# STC.net
KiCad netlist of a schematic drawn in Altium Designer
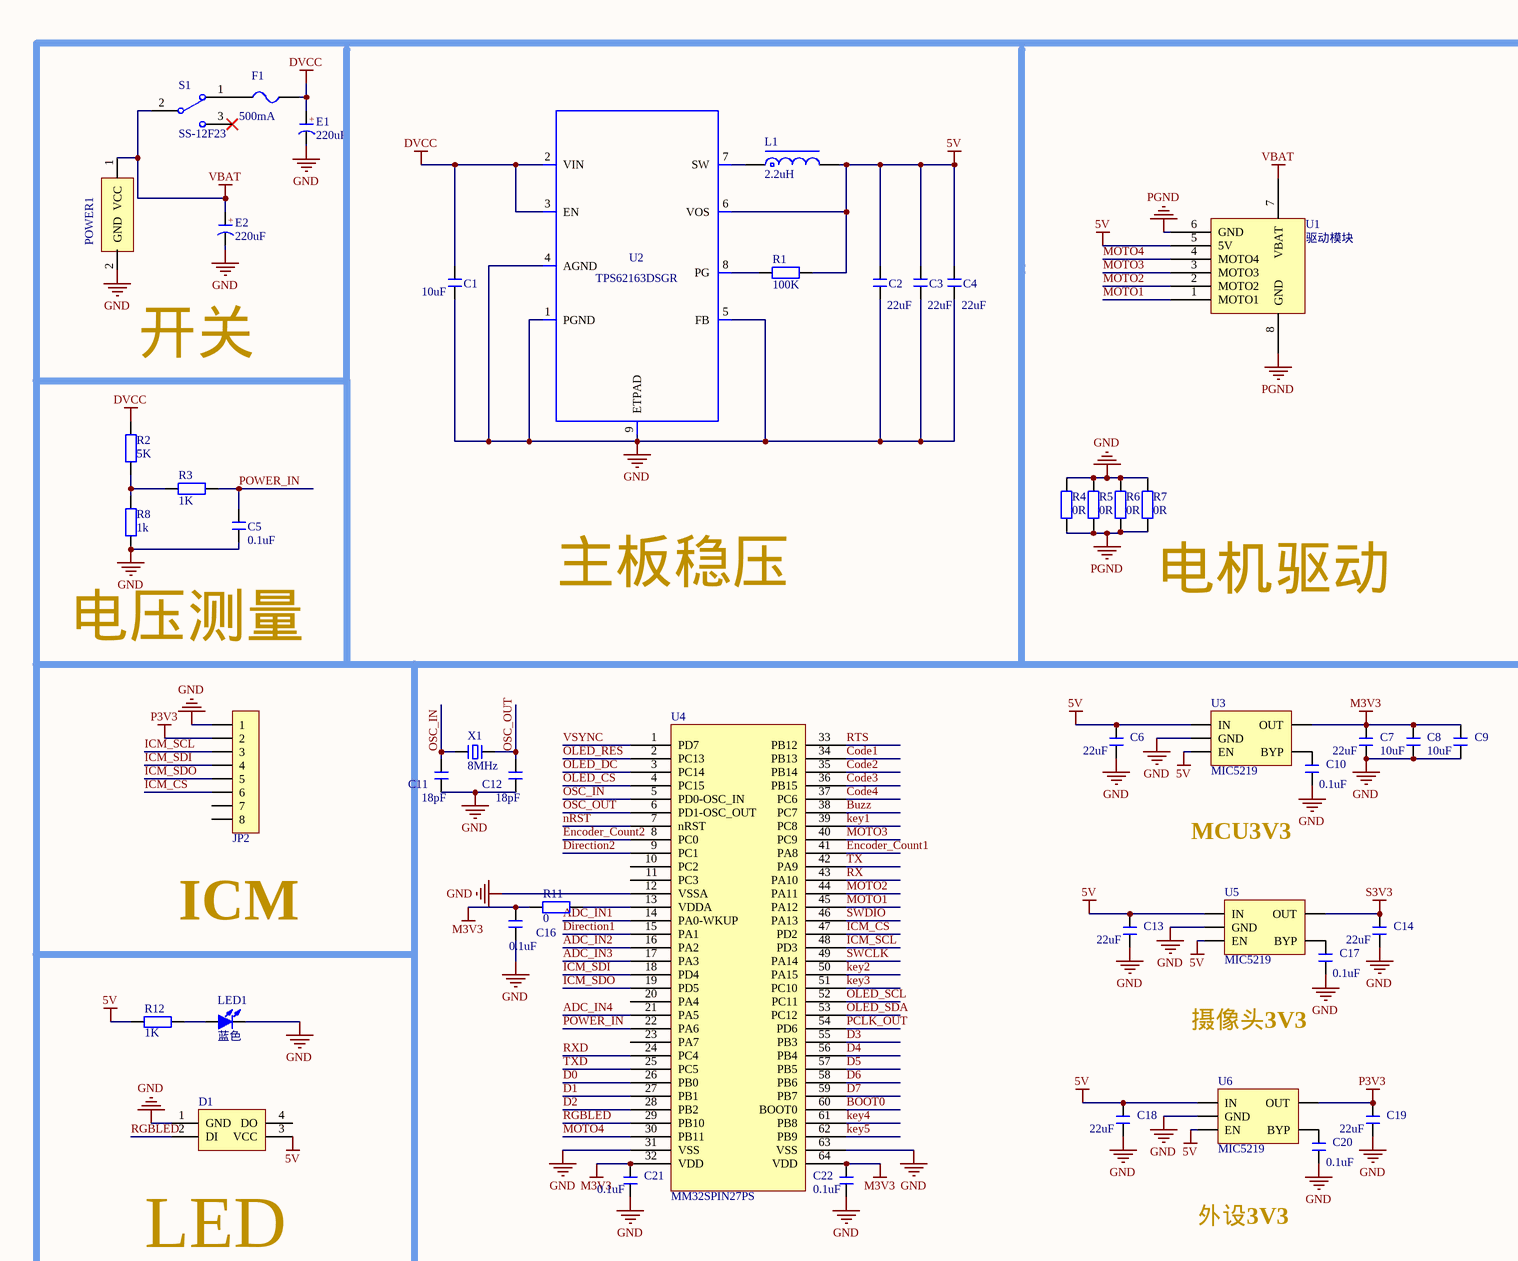
[diagram p0: STC智能车.SchDoc, top left]
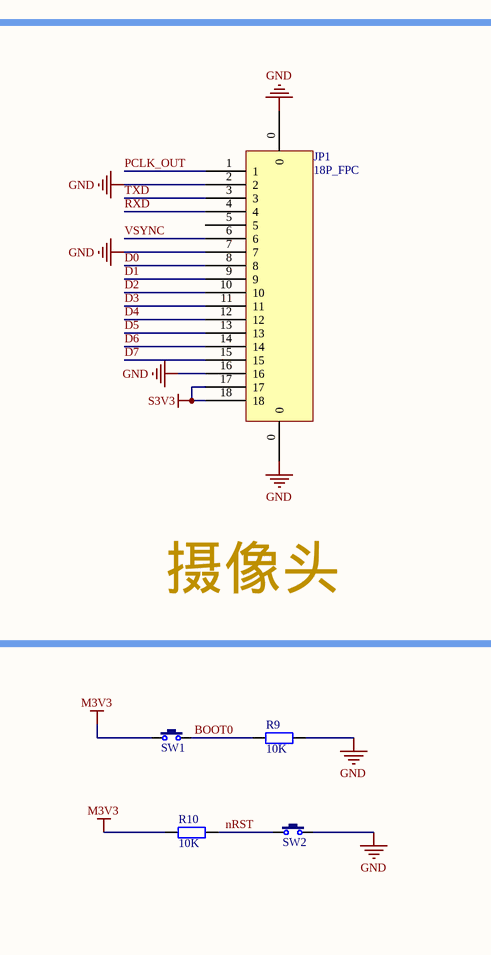
[diagram p1: STC智能车.SchDoc, top right]
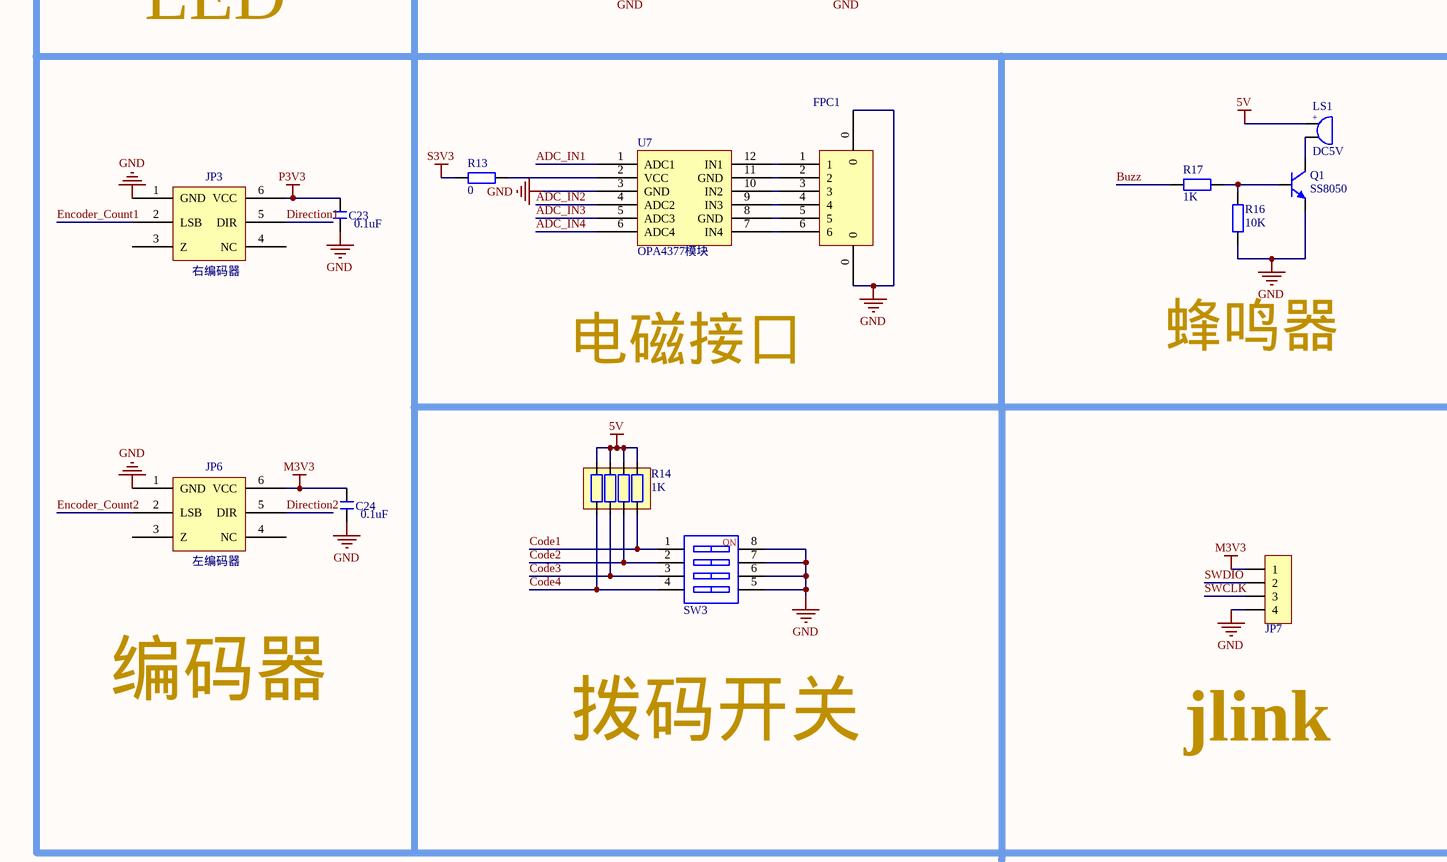
[diagram p2: STC智能车.SchDoc, bottom left]
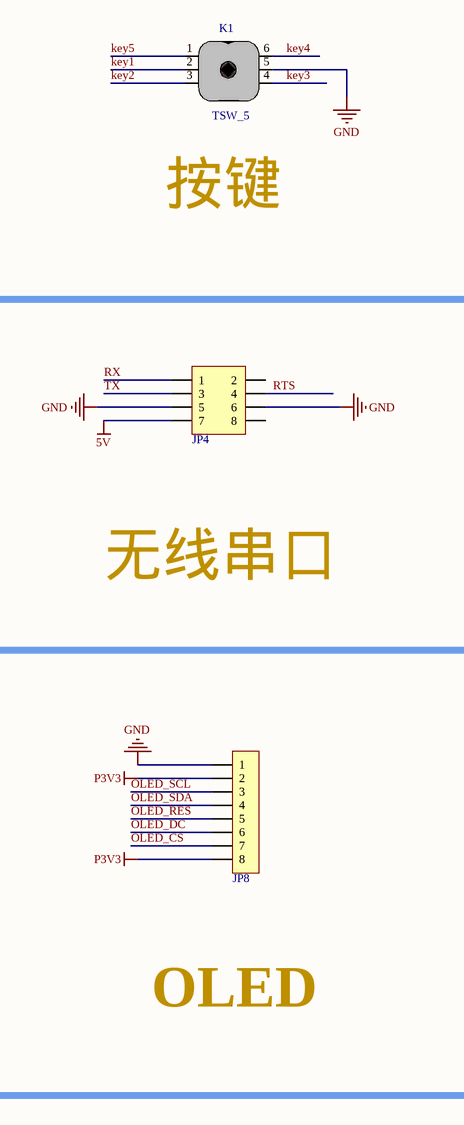
[diagram p3: STC智能车.SchDoc, bottom right]

(export (version "E")
  (design (tool "Eeschema 10.0.6"))
  (components
    (comp (ref "C1")
      (value "10uF")
      (footprint "C 0805_M")
      (description "贴片电容")
      (libsource (lib "0.1 - 电阻-电容-电感") (part "C"))
    )
    (comp (ref "C2")
      (value "22uF")
      (footprint "C 0805_M")
      (description "贴片电容")
      (libsource (lib "0.1 - 电阻-电容-电感") (part "C"))
    )
    (comp (ref "C3")
      (value "22uF")
      (footprint "C 0805_M")
      (description "贴片电容")
      (libsource (lib "0.1 - 电阻-电容-电感") (part "C"))
    )
    (comp (ref "C4")
      (value "22uF")
      (footprint "C 0805_M")
      (description "贴片电容")
      (libsource (lib "0.1 - 电阻-电容-电感") (part "C"))
    )
    (comp (ref "C5")
      (value "0.1uF")
      (footprint "C 0805_M")
      (description "贴片电容")
      (libsource (lib "0.1 - 电阻-电容-电感") (part "C"))
    )
    (comp (ref "C6")
      (value "22uF")
      (footprint "C 0805_M")
      (description "贴片电容")
      (libsource (lib "0.1 - 电阻-电容-电感") (part "C"))
    )
    (comp (ref "C7")
      (value "22uF")
      (footprint "C 0805_M")
      (description "贴片电容")
      (libsource (lib "0.1 - 电阻-电容-电感") (part "C"))
    )
    (comp (ref "C8")
      (value "10uF")
      (footprint "C 0805_M")
      (description "贴片电容")
      (libsource (lib "0.1 - 电阻-电容-电感") (part "C"))
    )
    (comp (ref "C9")
      (value "10uF")
      (footprint "C 0805_M")
      (description "贴片电容")
      (libsource (lib "0.1 - 电阻-电容-电感") (part "C"))
    )
    (comp (ref "C10")
      (value "0.1uF")
      (footprint "C 0805_M")
      (description "贴片电容")
      (libsource (lib "0.1 - 电阻-电容-电感") (part "C"))
    )
    (comp (ref "C11")
      (value "18pF")
      (footprint "C 0805_M")
      (description "贴片电容")
      (libsource (lib "0.1 - 电阻-电容-电感") (part "C"))
    )
    (comp (ref "C12")
      (value "18pF")
      (footprint "C 0805_M")
      (description "贴片电容")
      (libsource (lib "0.1 - 电阻-电容-电感") (part "C"))
    )
    (comp (ref "C13")
      (value "22uF")
      (footprint "C 0805_M")
      (description "贴片电容")
      (libsource (lib "0.1 - 电阻-电容-电感") (part "C"))
    )
    (comp (ref "C14")
      (value "22uF")
      (footprint "C 0805_M")
      (description "贴片电容")
      (libsource (lib "0.1 - 电阻-电容-电感") (part "C"))
    )
    (comp (ref "C16")
      (value "0.1uF")
      (footprint "C 0805_M")
      (description "贴片电容")
      (libsource (lib "0.1 - 电阻-电容-电感") (part "C"))
    )
    (comp (ref "C17")
      (value "0.1uF")
      (footprint "C 0805_M")
      (description "贴片电容")
      (libsource (lib "0.1 - 电阻-电容-电感") (part "C"))
    )
    (comp (ref "C18")
      (value "22uF")
      (footprint "C 0805_M")
      (description "贴片电容")
      (libsource (lib "0.1 - 电阻-电容-电感") (part "C"))
    )
    (comp (ref "C19")
      (value "22uF")
      (footprint "C 0805_M")
      (description "贴片电容")
      (libsource (lib "0.1 - 电阻-电容-电感") (part "C"))
    )
    (comp (ref "C20")
      (value "0.1uF")
      (footprint "C 0805_M")
      (description "贴片电容")
      (libsource (lib "0.1 - 电阻-电容-电感") (part "C"))
    )
    (comp (ref "C21")
      (value "0.1uF")
      (footprint "C 0805_M")
      (description "贴片电容")
      (libsource (lib "0.1 - 电阻-电容-电感") (part "C"))
    )
    (comp (ref "C22")
      (value "0.1uF")
      (footprint "C 0805_M")
      (description "贴片电容")
      (libsource (lib "0.1 - 电阻-电容-电感") (part "C"))
    )
    (comp (ref "C23")
      (value "0.1uF")
      (footprint "C 0805_M")
      (description "贴片电容")
      (libsource (lib "0.1 - 电阻-电容-电感") (part "C"))
    )
    (comp (ref "C24")
      (value "0.1uF")
      (footprint "C 0805_M")
      (description "贴片电容")
      (libsource (lib "0.1 - 电阻-电容-电感") (part "C"))
    )
    (comp (ref "D1")
      (value "P923D")
      (footprint "RGB_LED_5050")
      (fields (field (name "PUBLISHER") "mazhongwei"))
      (libsource (lib "RoboFly") (part "P923D"))
    )
    (comp (ref "E1")
      (value "220uF")
      (footprint "CD D(7343)")
      (description "贴片钽电容")
      (libsource (lib "0.1 - 电阻-电容-电感") (part "CT"))
    )
    (comp (ref "E2")
      (value "220uF")
      (footprint "CD D(7343)")
      (description "贴片钽电容")
      (libsource (lib "0.1 - 电阻-电容-电感") (part "CT"))
    )
    (comp (ref "F1")
      (value "500mA")
      (footprint "FU 0805")
      (description "贴片保险丝")
      (fields (field (name "版权归属") "源创客"))
      (libsource (lib "2.0 - 保险丝-晶振-光耦") (part "FU"))
    )
    (comp (ref "FPC1")
      (value "FPC_6PIN")
      (footprint "FPC0.5 2H-WS-6P")
      (libsource (lib "STC智能车") (part "FPC_6PIN"))
    )
    (comp (ref "JP1")
      (value "18P_FPC")
      (footprint "FPC0.5 2H-WS-18P")
      (libsource (lib "STC智能车") (part "18P_FPC"))
    )
    (comp (ref "JP2")
      (value "HDR-1X8")
      (footprint "XH2.54-WI-8P")
      (description "8P接插件")
      (fields (field (name "版权归属") "封装库来自淘宝 ID：黄晶宝石"))
      (libsource (lib "5.3 - 接插件-脚距2.54 (100mil) ") (part "Header 8"))
    )
    (comp (ref "JP3") (value "右编码器") (footprint "2*3牛插座") (libsource (lib "原理图库") (part "ENCODER")))
    (comp (ref "JP4")
      (value "Header 4X2")
      (footprint "HDR2.54-LI-2x4P")
      (description "4*2P接插件")
      (fields (field (name "版权归属") "封装库来自淘宝 ID：黄晶宝石"))
      (libsource (lib "5.3 - 接插件-脚距2.54 (100mil) ") (part "Header 4X2"))
    )
    (comp (ref "JP6") (value "左编码器") (footprint "2*3牛插座") (libsource (lib "原理图库") (part "ENCODER")))
    (comp (ref "JP7")
      (value "HDR-1X4")
      (footprint "XH2.54-WI-4P")
      (description "4P接插件")
      (fields (field (name "版权归属") "封装库来自淘宝 ID：黄晶宝石"))
      (libsource (lib "5.3 - 接插件-脚距2.54 (100mil) ") (part "Header 4"))
    )
    (comp (ref "JP8")
      (value "HDR-1X8")
      (footprint "IPS")
      (description "8P接插件")
      (fields (field (name "版权归属") "封装库来自淘宝 ID：黄晶宝石"))
      (libsource (lib "5.3 - 接插件-脚距2.54 (100mil) ") (part "Header 8"))
    )
    (comp (ref "K1")
      (value "TSW_5")
      (footprint "TSW-10")
      (description "方向开关")
      (libsource (lib "My Footprint") (part "TSW_5"))
    )
    (comp (ref "L1")
      (value "2.2uH")
      (footprint "CD52")
      (description "CD系列贴片线绕功率电感")
      (libsource (lib "0.1 - 电阻-电容-电感") (part "L-SMD"))
    )
    (comp (ref "LED1")
      (value "蓝色")
      (footprint "LED 0805B")
      (description "贴片LED")
      (fields (field (name "版权归属") "封装库来自淘宝 ID：黄晶宝石"))
      (libsource (lib "0.3 - LED发光二极管") (part "LED-SMD"))
    )
    (comp (ref "LS1")
      (value "DC5V")
      (footprint "BEEP 5x9x5.5")
      (description "蜂鸣器")
      (fields (field (name "版权归属") "封装库来自淘宝 ID：黄晶宝石"))
      (libsource (lib "4.1 - 未分类器件") (part "BEEP"))
    )
    (comp (ref "POWER1") (value "~") (footprint "T槽") (libsource (lib "原理图库") (part "T槽")))
    (comp (ref "Q1")
      (value "SS8050")
      (footprint "SOT23-3N")
      (description "高频放大-NPN型")
      (fields (field (name "版权归属") "封装库来自淘宝 ID：黄晶宝石"))
      (libsource (lib "0.4 - 三极管") (part "8050-SMD"))
    )
    (comp (ref "R1")
      (value "100K")
      (footprint "R 0805_M")
      (description "Resistor")
      (fields (field (name "Comment") "Res2") (field (name "PUBLISHER") "Altium Limited"))
      (libsource (lib "双电机节能车主板原理图库") (part "Res2"))
    )
    (comp (ref "R2")
      (value "5K")
      (footprint "R 0805_M")
      (description "Resistor")
      (fields (field (name "Comment") "Res2") (field (name "PUBLISHER") "Altium Limited"))
      (libsource (lib "") (part "Res2_1"))
    )
    (comp (ref "R3")
      (value "1K")
      (footprint "R 0805_M")
      (description "Resistor")
      (fields (field (name "Comment") "Res2") (field (name "PUBLISHER") "Altium Limited"))
      (libsource (lib "双电机节能车主板原理图库") (part "Res2"))
    )
    (comp (ref "R4") (value "0R") (footprint "R 0805_M") (libsource (lib "飞思卡尔") (part "RES")))
    (comp (ref "R5") (value "0R") (footprint "R 0805_M") (libsource (lib "飞思卡尔") (part "RES")))
    (comp (ref "R6") (value "0R") (footprint "R 0805_M") (libsource (lib "飞思卡尔") (part "RES")))
    (comp (ref "R7") (value "0R") (footprint "R 0805_M") (libsource (lib "飞思卡尔") (part "RES")))
    (comp (ref "R8")
      (value "1k")
      (footprint "R 0805_M")
      (description "Resistor")
      (fields (field (name "Comment") "Res2") (field (name "PUBLISHER") "Altium Limited"))
      (libsource (lib "") (part "Res2_1"))
    )
    (comp (ref "R9") (value "10K") (footprint "R 0805_M") (libsource (lib "") (part "RES_2")))
    (comp (ref "R10") (value "10K") (footprint "R 0805_M") (libsource (lib "") (part "RES_2")))
    (comp (ref "R11") (value "0") (footprint "R 0805_M") (libsource (lib "") (part "RES_1")))
    (comp (ref "R12")
      (value "1K")
      (footprint "R 0805_M")
      (description "Resistor")
      (fields (field (name "Comment") "Res2") (field (name "PUBLISHER") "Altium Limited"))
      (libsource (lib "双电机节能车主板原理图库") (part "Res2"))
    )
    (comp (ref "R13")
      (value "0")
      (footprint "R 0805_L")
      (description "贴片电阻")
      (fields (field (name "版权归属") "来自淘宝 ID：黄晶宝石"))
      (libsource (lib "0.1 - 电阻-电容-电感") (part "R"))
    )
    (comp (ref "R14")
      (value "1K")
      (footprint "RCA-8P4R-0603")
      (description "贴片排阻")
      (fields (field (name "版权归属") "封装库来自淘宝 ID：黄晶宝石"))
      (libsource (lib "0.1 - 电阻-电容-电感") (part "R-8P4R"))
    )
    (comp (ref "R16")
      (value "10K")
      (footprint "R 0805_L")
      (description "贴片电阻")
      (fields (field (name "版权归属") "来自淘宝 ID：黄晶宝石"))
      (libsource (lib "0.1 - 电阻-电容-电感") (part "R"))
    )
    (comp (ref "R17")
      (value "1K")
      (footprint "R 0805_L")
      (description "贴片电阻")
      (fields (field (name "版权归属") "来自淘宝 ID：黄晶宝石"))
      (libsource (lib "0.1 - 电阻-电容-电感") (part "R"))
    )
    (comp (ref "S1")
      (value "SS-12F23")
      (footprint "SS-12D10")
      (description "1路波动开关")
      (fields (field (name "版权归属") "封装库来自淘宝 ID：黄晶宝石"))
      (libsource (lib "0.7 - 常用按键-开关") (part "SSW-1P"))
    )
    (comp (ref "SW1")
      (value "3x6x5")
      (footprint "TSW SMD-3*6*2.5")
      (description "3x6轻触开关")
      (fields (field (name "版权归属") "封装库来自淘宝 ID：黄晶宝石"))
      (libsource (lib "0.7 - 常用按键-开关") (part "TSW 3x6"))
    )
    (comp (ref "SW2")
      (value "3x6x5")
      (footprint "TSW SMD-3*6*2.5")
      (description "3x6轻触开关")
      (fields (field (name "版权归属") "封装库来自淘宝 ID：黄晶宝石"))
      (libsource (lib "0.7 - 常用按键-开关") (part "TSW 3x6"))
    )
    (comp (ref "SW3")
      (value "SW-4P")
      (footprint "CSW DIP-4P")
      (description "4路编码开关")
      (libsource (lib "0.7 - 常用按键-开关") (part "SW-4P"))
    )
    (comp (ref "U1") (value "驱动模块") (footprint "电机驱动") (libsource (lib "STC智能车") (part "驱动模块")))
    (comp (ref "U2")
      (value "TPS62163DSGR")
      (footprint "TPS62163")
      (fields (field (name "PACKAGEREFERENCE") "TPS62163DSGR"))
      (libsource (lib "TI WEBENCH") (part "U1"))
    )
    (comp (ref "U3") (value "MIC5219") (footprint "SOT23-5M") (libsource (lib "TI") (part "MIC5219")))
    (comp (ref "U4")
      (value "MM32SPIN27PS")
      (footprint "LQFP64 10x10_M")
      (libsource (lib "STC智能车") (part "MM32SPIN27PS"))
    )
    (comp (ref "U5") (value "MIC5219") (footprint "SOT23-5M") (libsource (lib "TI") (part "MIC5219")))
    (comp (ref "U6") (value "MIC5219") (footprint "SOT23-5M") (libsource (lib "TI") (part "MIC5219")))
    (comp (ref "U7")
      (value "OPA4377模块")
      (footprint "OPA4377模块")
      (libsource (lib "STC智能车") (part "OPA4377模块"))
    )
    (comp (ref "X1")
      (value "8MHz")
      (footprint "OSC 5032-2P")
      (description "2脚无源脚晶振")
      (fields (field (name "版权归属") "源创客"))
      (libsource (lib "2.0 - 保险丝-晶振-光耦") (part "XTAL-2P"))
    )
  )
  (nets
    (net (code "1") (name "/ADC_IN1") (class "Default")
      (node (ref "U4") (pin "14") (pinfunction "PA0-WKUP_14") (pintype "passive"))
      (node (ref "U7") (pin "1") (pinfunction "ADC1_1") (pintype "passive"))
    )
    (net (code "2") (name "/ADC_IN2") (class "Default")
      (node (ref "U4") (pin "16") (pinfunction "PA2_16") (pintype "passive"))
      (node (ref "U7") (pin "4") (pinfunction "ADC2_4") (pintype "passive"))
    )
    (net (code "3") (name "/ADC_IN3") (class "Default")
      (node (ref "U4") (pin "17") (pinfunction "PA3_17") (pintype "passive"))
      (node (ref "U7") (pin "5") (pinfunction "ADC3_5") (pintype "passive"))
    )
    (net (code "4") (name "/ADC_IN4") (class "Default")
      (node (ref "U4") (pin "21") (pinfunction "PA5_21") (pintype "passive"))
      (node (ref "U7") (pin "6") (pinfunction "ADC4_6") (pintype "passive"))
    )
    (net (code "5") (name "/BOOT0") (class "Default")
      (node (ref "R9") (pin "1") (pinfunction "1_1") (pintype "passive"))
      (node (ref "SW1") (pin "2") (pinfunction "2_2") (pintype "passive"))
      (node (ref "U4") (pin "60") (pinfunction "BOOT0_60") (pintype "passive"))
    )
    (net (code "6") (name "/Buzz") (class "Default")
      (node (ref "R17") (pin "2") (pinfunction "2_2") (pintype "passive"))
      (node (ref "U4") (pin "38") (pinfunction "PC7_38") (pintype "passive"))
    )
    (net (code "7") (name "/Code1") (class "Default")
      (node (ref "R14") (pin "4") (pinfunction "4_4") (pintype "passive"))
      (node (ref "SW3") (pin "1") (pinfunction "1_1") (pintype "passive"))
      (node (ref "U4") (pin "34") (pinfunction "PB13_34") (pintype "passive"))
    )
    (net (code "8") (name "/Code2") (class "Default")
      (node (ref "R14") (pin "3") (pinfunction "3_3") (pintype "passive"))
      (node (ref "SW3") (pin "2") (pinfunction "2_2") (pintype "passive"))
      (node (ref "U4") (pin "35") (pinfunction "PB14_35") (pintype "passive"))
    )
    (net (code "9") (name "/Code3") (class "Default")
      (node (ref "R14") (pin "2") (pinfunction "2_2") (pintype "passive"))
      (node (ref "SW3") (pin "3") (pinfunction "3_3") (pintype "passive"))
      (node (ref "U4") (pin "36") (pinfunction "PB15_36") (pintype "passive"))
    )
    (net (code "10") (name "/Code4") (class "Default")
      (node (ref "R14") (pin "1") (pinfunction "1_1") (pintype "passive"))
      (node (ref "SW3") (pin "4") (pinfunction "4_4") (pintype "passive"))
      (node (ref "U4") (pin "37") (pinfunction "PC6_37") (pintype "passive"))
    )
    (net (code "11") (name "/D0") (class "Default")
      (node (ref "JP1") (pin "8") (pinfunction "8_8") (pintype "passive"))
      (node (ref "U4") (pin "26") (pinfunction "PB0_26") (pintype "passive"))
    )
    (net (code "12") (name "/D1") (class "Default")
      (node (ref "JP1") (pin "9") (pinfunction "9_9") (pintype "passive"))
      (node (ref "U4") (pin "27") (pinfunction "PB1_27") (pintype "passive"))
    )
    (net (code "13") (name "/D2") (class "Default")
      (node (ref "JP1") (pin "10") (pinfunction "10_10") (pintype "passive"))
      (node (ref "U4") (pin "28") (pinfunction "PB2_28") (pintype "passive"))
    )
    (net (code "14") (name "/D3") (class "Default")
      (node (ref "JP1") (pin "11") (pinfunction "11_11") (pintype "passive"))
      (node (ref "U4") (pin "55") (pinfunction "PB3_55") (pintype "passive"))
    )
    (net (code "15") (name "/D4") (class "Default")
      (node (ref "JP1") (pin "12") (pinfunction "12_12") (pintype "passive"))
      (node (ref "U4") (pin "56") (pinfunction "PB4_56") (pintype "passive"))
    )
    (net (code "16") (name "/D5") (class "Default")
      (node (ref "JP1") (pin "13") (pinfunction "13_13") (pintype "passive"))
      (node (ref "U4") (pin "57") (pinfunction "PB5_57") (pintype "passive"))
    )
    (net (code "17") (name "/D6") (class "Default")
      (node (ref "JP1") (pin "14") (pinfunction "14_14") (pintype "passive"))
      (node (ref "U4") (pin "58") (pinfunction "PB6_58") (pintype "passive"))
    )
    (net (code "18") (name "/D7") (class "Default")
      (node (ref "JP1") (pin "15") (pinfunction "15_15") (pintype "passive"))
      (node (ref "U4") (pin "59") (pinfunction "PB7_59") (pintype "passive"))
    )
    (net (code "19") (name "/Direction1") (class "Default")
      (node (ref "JP3") (pin "5") (pinfunction "DIR_5") (pintype "passive"))
      (node (ref "U4") (pin "15") (pinfunction "PA1_15") (pintype "passive"))
    )
    (net (code "20") (name "/Direction2") (class "Default")
      (node (ref "JP6") (pin "5") (pinfunction "DIR_5") (pintype "passive"))
      (node (ref "U4") (pin "9") (pinfunction "PC1_9") (pintype "passive"))
    )
    (net (code "21") (name "/Encoder_Count1") (class "Default")
      (node (ref "JP3") (pin "2") (pinfunction "LSB_2") (pintype "passive"))
      (node (ref "U4") (pin "41") (pinfunction "PA8_41") (pintype "passive"))
    )
    (net (code "22") (name "/Encoder_Count2") (class "Default")
      (node (ref "JP6") (pin "2") (pinfunction "LSB_2") (pintype "passive"))
      (node (ref "U4") (pin "8") (pinfunction "PC0_8") (pintype "passive"))
    )
    (net (code "23") (name "/ICM_CS") (class "Default")
      (node (ref "JP2") (pin "6") (pinfunction "6_6") (pintype "passive"))
      (node (ref "U4") (pin "47") (pinfunction "PD2_47") (pintype "passive"))
    )
    (net (code "24") (name "/ICM_SCL") (class "Default")
      (node (ref "JP2") (pin "3") (pinfunction "3_3") (pintype "passive"))
      (node (ref "U4") (pin "48") (pinfunction "PD3_48") (pintype "passive"))
    )
    (net (code "25") (name "/ICM_SDI") (class "Default")
      (node (ref "JP2") (pin "4") (pinfunction "4_4") (pintype "passive"))
      (node (ref "U4") (pin "18") (pinfunction "PD4_18") (pintype "passive"))
    )
    (net (code "26") (name "/ICM_SDO") (class "Default")
      (node (ref "JP2") (pin "5") (pinfunction "5_5") (pintype "passive"))
      (node (ref "U4") (pin "19") (pinfunction "PD5_19") (pintype "passive"))
    )
    (net (code "27") (name "/MOTO1") (class "Default")
      (node (ref "U1") (pin "1") (pinfunction "MOTO1_1") (pintype "passive"))
      (node (ref "U4") (pin "45") (pinfunction "PA12_45") (pintype "passive"))
    )
    (net (code "28") (name "/MOTO2") (class "Default")
      (node (ref "U1") (pin "2") (pinfunction "MOTO2_2") (pintype "passive"))
      (node (ref "U4") (pin "44") (pinfunction "PA11_44") (pintype "passive"))
    )
    (net (code "29") (name "/MOTO3") (class "Default")
      (node (ref "U1") (pin "3") (pinfunction "MOTO3_3") (pintype "passive"))
      (node (ref "U4") (pin "40") (pinfunction "PC9_40") (pintype "passive"))
    )
    (net (code "30") (name "/MOTO4") (class "Default")
      (node (ref "U1") (pin "4") (pinfunction "MOTO4_4") (pintype "passive"))
      (node (ref "U4") (pin "30") (pinfunction "PB11_30") (pintype "passive"))
    )
    (net (code "31") (name "/OLED_CS") (class "Default")
      (node (ref "JP8") (pin "7") (pinfunction "7_7") (pintype "passive"))
      (node (ref "U4") (pin "4") (pinfunction "PC15_4") (pintype "passive"))
    )
    (net (code "32") (name "/OLED_DC") (class "Default")
      (node (ref "JP8") (pin "6") (pinfunction "6_6") (pintype "passive"))
      (node (ref "U4") (pin "3") (pinfunction "PC14_3") (pintype "passive"))
    )
    (net (code "33") (name "/OLED_RES") (class "Default")
      (node (ref "JP8") (pin "5") (pinfunction "5_5") (pintype "passive"))
      (node (ref "U4") (pin "2") (pinfunction "PC13_2") (pintype "passive"))
    )
    (net (code "34") (name "/OLED_SCL") (class "Default")
      (node (ref "JP8") (pin "3") (pinfunction "3_3") (pintype "passive"))
      (node (ref "U4") (pin "52") (pinfunction "PC11_52") (pintype "passive"))
    )
    (net (code "35") (name "/OLED_SDA") (class "Default")
      (node (ref "JP8") (pin "4") (pinfunction "4_4") (pintype "passive"))
      (node (ref "U4") (pin "53") (pinfunction "PC12_53") (pintype "passive"))
    )
    (net (code "36") (name "/OSC_IN") (class "Default")
      (node (ref "C11") (pin "2") (pinfunction "2_2") (pintype "passive"))
      (node (ref "U4") (pin "5") (pinfunction "PD0-OSC_IN_5") (pintype "passive"))
      (node (ref "X1") (pin "1") (pinfunction "1_1") (pintype "passive"))
    )
    (net (code "37") (name "/OSC_OUT") (class "Default")
      (node (ref "C12") (pin "2") (pinfunction "2_2") (pintype "passive"))
      (node (ref "U4") (pin "6") (pinfunction "PD1-OSC_OUT_6") (pintype "passive"))
      (node (ref "X1") (pin "2") (pinfunction "2_2") (pintype "passive"))
    )
    (net (code "38") (name "/PCLK_OUT") (class "Default")
      (node (ref "JP1") (pin "1") (pinfunction "1_1") (pintype "passive"))
      (node (ref "U4") (pin "54") (pinfunction "PD6_54") (pintype "passive"))
    )
    (net (code "39") (name "/POWER_IN") (class "Default")
      (node (ref "C5") (pin "2") (pinfunction "2_2") (pintype "passive"))
      (node (ref "R3") (pin "1") (pinfunction "1_1") (pintype "passive"))
      (node (ref "U4") (pin "22") (pinfunction "PA6_22") (pintype "passive"))
    )
    (net (code "40") (name "/RGBLED") (class "Default")
      (node (ref "D1") (pin "2") (pinfunction "DI_2") (pintype "passive"))
      (node (ref "U4") (pin "29") (pinfunction "PB10_29") (pintype "passive"))
    )
    (net (code "41") (name "/RTS") (class "Default")
      (node (ref "JP4") (pin "4") (pinfunction "4_4") (pintype "passive"))
      (node (ref "U4") (pin "33") (pinfunction "PB12_33") (pintype "passive"))
    )
    (net (code "42") (name "/RX") (class "Default")
      (node (ref "JP4") (pin "1") (pinfunction "1_1") (pintype "passive"))
      (node (ref "U4") (pin "43") (pinfunction "PA10_43") (pintype "passive"))
    )
    (net (code "43") (name "/RXD") (class "Default")
      (node (ref "JP1") (pin "4") (pinfunction "4_4") (pintype "passive"))
      (node (ref "U4") (pin "24") (pinfunction "PC4_24") (pintype "passive"))
    )
    (net (code "44") (name "/SWCLK") (class "Default")
      (node (ref "JP7") (pin "3") (pinfunction "3_3") (pintype "passive"))
      (node (ref "U4") (pin "49") (pinfunction "PA14_49") (pintype "passive"))
    )
    (net (code "45") (name "/SWDIO") (class "Default")
      (node (ref "JP7") (pin "2") (pinfunction "2_2") (pintype "passive"))
      (node (ref "U4") (pin "46") (pinfunction "PA13_46") (pintype "passive"))
    )
    (net (code "46") (name "/TX") (class "Default")
      (node (ref "JP4") (pin "3") (pinfunction "3_3") (pintype "passive"))
      (node (ref "U4") (pin "42") (pinfunction "PA9_42") (pintype "passive"))
    )
    (net (code "47") (name "/TXD") (class "Default")
      (node (ref "JP1") (pin "3") (pinfunction "3_3") (pintype "passive"))
      (node (ref "U4") (pin "25") (pinfunction "PC5_25") (pintype "passive"))
    )
    (net (code "48") (name "/VSYNC") (class "Default")
      (node (ref "JP1") (pin "6") (pinfunction "6_6") (pintype "passive"))
      (node (ref "U4") (pin "1") (pinfunction "PD7_1") (pintype "passive"))
    )
    (net (code "49") (name "/key1") (class "Default")
      (node (ref "K1") (pin "2") (pintype "passive"))
      (node (ref "U4") (pin "39") (pinfunction "PC8_39") (pintype "passive"))
    )
    (net (code "50") (name "/key2") (class "Default")
      (node (ref "K1") (pin "3") (pintype "passive"))
      (node (ref "U4") (pin "50") (pinfunction "PA15_50") (pintype "passive"))
    )
    (net (code "51") (name "/key3") (class "Default")
      (node (ref "K1") (pin "4") (pintype "passive"))
      (node (ref "U4") (pin "51") (pinfunction "PC10_51") (pintype "passive"))
    )
    (net (code "52") (name "/key4") (class "Default")
      (node (ref "K1") (pin "6") (pintype "passive"))
      (node (ref "U4") (pin "61") (pinfunction "PB8_61") (pintype "passive"))
    )
    (net (code "53") (name "/key5") (class "Default")
      (node (ref "K1") (pin "1") (pintype "passive"))
      (node (ref "U4") (pin "62") (pinfunction "PB9_62") (pintype "passive"))
    )
    (net (code "54") (name "/nRST") (class "Default")
      (node (ref "R10") (pin "2") (pinfunction "2_2") (pintype "passive"))
      (node (ref "SW2") (pin "1") (pinfunction "1_1") (pintype "passive"))
      (node (ref "U4") (pin "7") (pinfunction "nRST_7") (pintype "passive"))
    )
    (net (code "55") (name "5V") (class "Default")
      (node (ref "C13") (pin "2") (pinfunction "2_2") (pintype "passive"))
      (node (ref "C18") (pin "2") (pinfunction "2_2") (pintype "passive"))
      (node (ref "C2") (pin "2") (pinfunction "2_2") (pintype "passive"))
      (node (ref "C3") (pin "2") (pinfunction "2_2") (pintype "passive"))
      (node (ref "C4") (pin "2") (pinfunction "2_2") (pintype "passive"))
      (node (ref "C6") (pin "2") (pinfunction "2_2") (pintype "passive"))
      (node (ref "D1") (pin "3") (pinfunction "VCC_3") (pintype "passive"))
      (node (ref "JP4") (pin "7") (pinfunction "7_7") (pintype "passive"))
      (node (ref "L1") (pin "2") (pinfunction "2_2") (pintype "passive"))
      (node (ref "LS1") (pin "1") (pinfunction "1_1") (pintype "passive"))
      (node (ref "R1") (pin "1") (pinfunction "1_1") (pintype "passive"))
      (node (ref "R12") (pin "2") (pinfunction "2_2") (pintype "passive"))
      (node (ref "R14") (pin "5") (pinfunction "5_5") (pintype "passive"))
      (node (ref "R14") (pin "6") (pinfunction "6_6") (pintype "passive"))
      (node (ref "R14") (pin "7") (pinfunction "7_7") (pintype "passive"))
      (node (ref "R14") (pin "8") (pinfunction "8_8") (pintype "passive"))
      (node (ref "U1") (pin "5") (pinfunction "5V_5") (pintype "passive"))
      (node (ref "U2") (pin "6") (pinfunction "VOS_6") (pintype "passive"))
      (node (ref "U3") (pin "1") (pinfunction "IN_1") (pintype "passive"))
      (node (ref "U3") (pin "3") (pinfunction "EN_3") (pintype "passive"))
      (node (ref "U5") (pin "1") (pinfunction "IN_1") (pintype "passive"))
      (node (ref "U5") (pin "3") (pinfunction "EN_3") (pintype "passive"))
      (node (ref "U6") (pin "1") (pinfunction "IN_1") (pintype "passive"))
      (node (ref "U6") (pin "3") (pinfunction "EN_3") (pintype "passive"))
    )
    (net (code "56") (name "DVCC") (class "Default")
      (node (ref "C1") (pin "2") (pinfunction "2_2") (pintype "passive"))
      (node (ref "E1") (pin "1") (pinfunction "A_1") (pintype "passive"))
      (node (ref "F1") (pin "2") (pinfunction "2_2") (pintype "passive"))
      (node (ref "R2") (pin "2") (pinfunction "2_2") (pintype "passive"))
      (node (ref "U2") (pin "2") (pinfunction "VIN_2") (pintype "passive"))
      (node (ref "U2") (pin "3") (pinfunction "EN_3") (pintype "passive"))
    )
    (net (code "57") (name "GND") (class "Default")
      (node (ref "C1") (pin "1") (pinfunction "1_1") (pintype "passive"))
      (node (ref "C10") (pin "1") (pinfunction "1_1") (pintype "passive"))
      (node (ref "C11") (pin "1") (pinfunction "1_1") (pintype "passive"))
      (node (ref "C12") (pin "1") (pinfunction "1_1") (pintype "passive"))
      (node (ref "C13") (pin "1") (pinfunction "1_1") (pintype "passive"))
      (node (ref "C14") (pin "1") (pinfunction "1_1") (pintype "passive"))
      (node (ref "C16") (pin "1") (pinfunction "1_1") (pintype "passive"))
      (node (ref "C17") (pin "1") (pinfunction "1_1") (pintype "passive"))
      (node (ref "C18") (pin "1") (pinfunction "1_1") (pintype "passive"))
      (node (ref "C19") (pin "1") (pinfunction "1_1") (pintype "passive"))
      (node (ref "C2") (pin "1") (pinfunction "1_1") (pintype "passive"))
      (node (ref "C20") (pin "1") (pinfunction "1_1") (pintype "passive"))
      (node (ref "C21") (pin "1") (pinfunction "1_1") (pintype "passive"))
      (node (ref "C22") (pin "1") (pinfunction "1_1") (pintype "passive"))
      (node (ref "C23") (pin "1") (pinfunction "1_1") (pintype "passive"))
      (node (ref "C24") (pin "1") (pinfunction "1_1") (pintype "passive"))
      (node (ref "C3") (pin "1") (pinfunction "1_1") (pintype "passive"))
      (node (ref "C4") (pin "1") (pinfunction "1_1") (pintype "passive"))
      (node (ref "C5") (pin "1") (pinfunction "1_1") (pintype "passive"))
      (node (ref "C6") (pin "1") (pinfunction "1_1") (pintype "passive"))
      (node (ref "C7") (pin "1") (pinfunction "1_1") (pintype "passive"))
      (node (ref "C8") (pin "1") (pinfunction "1_1") (pintype "passive"))
      (node (ref "C9") (pin "1") (pinfunction "1_1") (pintype "passive"))
      (node (ref "D1") (pin "1") (pinfunction "GND_1") (pintype "passive"))
      (node (ref "E1") (pin "2") (pinfunction "K_2") (pintype "passive"))
      (node (ref "E2") (pin "2") (pinfunction "K_2") (pintype "passive"))
      (node (ref "FPC1") (pin "0") (pinfunction "0_0") (pintype "passive"))
      (node (ref "JP1") (pin "0") (pinfunction "0_0") (pintype "passive"))
      (node (ref "JP1") (pin "16") (pinfunction "16_16") (pintype "passive"))
      (node (ref "JP1") (pin "2") (pinfunction "2_2") (pintype "passive"))
      (node (ref "JP1") (pin "7") (pinfunction "7_7") (pintype "passive"))
      (node (ref "JP2") (pin "1") (pinfunction "1_1") (pintype "passive"))
      (node (ref "JP3") (pin "1") (pinfunction "GND_1") (pintype "passive"))
      (node (ref "JP4") (pin "5") (pinfunction "5_5") (pintype "passive"))
      (node (ref "JP4") (pin "6") (pinfunction "6_6") (pintype "passive"))
      (node (ref "JP6") (pin "1") (pinfunction "GND_1") (pintype "passive"))
      (node (ref "JP7") (pin "4") (pinfunction "4_4") (pintype "passive"))
      (node (ref "JP8") (pin "1") (pinfunction "1_1") (pintype "passive"))
      (node (ref "K1") (pin "5") (pintype "passive"))
      (node (ref "LED1") (pin "2") (pinfunction "K_2") (pintype "passive"))
      (node (ref "POWER1") (pin "2") (pinfunction "GND_2") (pintype "passive"))
      (node (ref "Q1") (pin "2") (pinfunction "E_2") (pintype "passive"))
      (node (ref "R16") (pin "1") (pinfunction "1_1") (pintype "passive"))
      (node (ref "R4") (pin "2") (pinfunction "2_2") (pintype "passive"))
      (node (ref "R5") (pin "2") (pinfunction "2_2") (pintype "passive"))
      (node (ref "R6") (pin "2") (pinfunction "2_2") (pintype "passive"))
      (node (ref "R7") (pin "2") (pinfunction "2_2") (pintype "passive"))
      (node (ref "R8") (pin "1") (pinfunction "1_1") (pintype "passive"))
      (node (ref "R9") (pin "2") (pinfunction "2_2") (pintype "passive"))
      (node (ref "SW2") (pin "2") (pinfunction "2_2") (pintype "passive"))
      (node (ref "SW3") (pin "5") (pinfunction "5_5") (pintype "passive"))
      (node (ref "SW3") (pin "6") (pinfunction "6_6") (pintype "passive"))
      (node (ref "SW3") (pin "7") (pinfunction "7_7") (pintype "passive"))
      (node (ref "SW3") (pin "8") (pinfunction "8_8") (pintype "passive"))
      (node (ref "U2") (pin "1") (pinfunction "PGND_1") (pintype "passive"))
      (node (ref "U2") (pin "4") (pinfunction "AGND_4") (pintype "passive"))
      (node (ref "U2") (pin "5") (pinfunction "FB_5") (pintype "passive"))
      (node (ref "U2") (pin "9") (pinfunction "ETPAD_9") (pintype "passive"))
      (node (ref "U3") (pin "2") (pinfunction "GND_2") (pintype "passive"))
      (node (ref "U4") (pin "12") (pinfunction "VSSA_12") (pintype "passive"))
      (node (ref "U4") (pin "31") (pinfunction "VSS_31") (pintype "passive"))
      (node (ref "U4") (pin "63") (pinfunction "VSS_63") (pintype "passive"))
      (node (ref "U5") (pin "2") (pinfunction "GND_2") (pintype "passive"))
      (node (ref "U6") (pin "2") (pinfunction "GND_2") (pintype "passive"))
      (node (ref "U7") (pin "3") (pinfunction "GND_3") (pintype "passive"))
    )
    (net (code "58") (name "M3V3") (class "Default")
      (node (ref "C16") (pin "2") (pinfunction "2_2") (pintype "passive"))
      (node (ref "C21") (pin "2") (pinfunction "2_2") (pintype "passive"))
      (node (ref "C22") (pin "2") (pinfunction "2_2") (pintype "passive"))
      (node (ref "C24") (pin "2") (pinfunction "2_2") (pintype "passive"))
      (node (ref "C7") (pin "2") (pinfunction "2_2") (pintype "passive"))
      (node (ref "C8") (pin "2") (pinfunction "2_2") (pintype "passive"))
      (node (ref "C9") (pin "2") (pinfunction "2_2") (pintype "passive"))
      (node (ref "JP6") (pin "6") (pinfunction "VCC_6") (pintype "passive"))
      (node (ref "JP7") (pin "1") (pinfunction "1_1") (pintype "passive"))
      (node (ref "R10") (pin "1") (pinfunction "1_1") (pintype "passive"))
      (node (ref "R11") (pin "2") (pinfunction "2_2") (pintype "passive"))
      (node (ref "SW1") (pin "1") (pinfunction "1_1") (pintype "passive"))
      (node (ref "U3") (pin "5") (pinfunction "OUT_5") (pintype "passive"))
      (node (ref "U4") (pin "32") (pinfunction "VDD_32") (pintype "passive"))
      (node (ref "U4") (pin "64") (pinfunction "VDD_64") (pintype "passive"))
    )
    (net (code "59") (name "Net-(F1-Pad1)") (class "Default")
      (node (ref "F1") (pin "1") (pinfunction "1_1") (pintype "passive"))
      (node (ref "S1") (pin "1") (pinfunction "1_1") (pintype "passive"))
    )
    (net (code "60") (name "Net-(FPC1-Pad2)") (class "Default")
      (node (ref "FPC1") (pin "2") (pinfunction "2_2") (pintype "passive"))
      (node (ref "U7") (pin "11") (pinfunction "GND_11") (pintype "passive"))
    )
    (net (code "61") (name "Net-(FPC1-Pad5)") (class "Default")
      (node (ref "FPC1") (pin "5") (pinfunction "5_5") (pintype "passive"))
      (node (ref "U7") (pin "8") (pinfunction "GND_8") (pintype "passive"))
    )
    (net (code "62") (name "Net-(LED1-A)") (class "Default")
      (node (ref "LED1") (pin "1") (pinfunction "A_1") (pintype "passive"))
      (node (ref "R12") (pin "1") (pinfunction "1_1") (pintype "passive"))
    )
    (net (code "63") (name "Net-(Q1-B)") (class "Default")
      (node (ref "Q1") (pin "1") (pinfunction "B_1") (pintype "passive"))
      (node (ref "R16") (pin "2") (pinfunction "2_2") (pintype "passive"))
      (node (ref "R17") (pin "1") (pinfunction "1_1") (pintype "passive"))
    )
    (net (code "64") (name "Net-(Q1-C)") (class "Default")
      (node (ref "LS1") (pin "2") (pinfunction "2_2") (pintype "passive"))
      (node (ref "Q1") (pin "3") (pinfunction "C_3") (pintype "passive"))
    )
    (net (code "65") (name "Net-(R2-Pad1)") (class "Default")
      (node (ref "R2") (pin "1") (pinfunction "1_1") (pintype "passive"))
      (node (ref "R3") (pin "2") (pinfunction "2_2") (pintype "passive"))
      (node (ref "R8") (pin "2") (pinfunction "2_2") (pintype "passive"))
    )
    (net (code "66") (name "Net-(U2-PG)") (class "Default")
      (node (ref "R1") (pin "2") (pinfunction "2_2") (pintype "passive"))
      (node (ref "U2") (pin "8") (pinfunction "PG_8") (pintype "passive"))
    )
    (net (code "67") (name "Net-(U2-SW)") (class "Default")
      (node (ref "L1") (pin "1") (pinfunction "1_1") (pintype "passive"))
      (node (ref "U2") (pin "7") (pinfunction "SW_7") (pintype "passive"))
    )
    (net (code "68") (name "Net-(U3-BYP)") (class "Default")
      (node (ref "C10") (pin "2") (pinfunction "2_2") (pintype "passive"))
      (node (ref "U3") (pin "4") (pinfunction "BYP_4") (pintype "passive"))
    )
    (net (code "69") (name "Net-(U4-VDDA)") (class "Default")
      (node (ref "R11") (pin "1") (pinfunction "1_1") (pintype "passive"))
      (node (ref "U4") (pin "13") (pinfunction "VDDA_13") (pintype "passive"))
    )
    (net (code "70") (name "Net-(U5-BYP)") (class "Default")
      (node (ref "C17") (pin "2") (pinfunction "2_2") (pintype "passive"))
      (node (ref "U5") (pin "4") (pinfunction "BYP_4") (pintype "passive"))
    )
    (net (code "71") (name "Net-(U6-BYP)") (class "Default")
      (node (ref "C20") (pin "2") (pinfunction "2_2") (pintype "passive"))
      (node (ref "U6") (pin "4") (pinfunction "BYP_4") (pintype "passive"))
    )
    (net (code "72") (name "Net-(U7-IN1)") (class "Default")
      (node (ref "FPC1") (pin "1") (pinfunction "1_1") (pintype "passive"))
      (node (ref "U7") (pin "12") (pinfunction "IN1_12") (pintype "passive"))
    )
    (net (code "73") (name "Net-(U7-IN2)") (class "Default")
      (node (ref "FPC1") (pin "3") (pinfunction "3_3") (pintype "passive"))
      (node (ref "U7") (pin "10") (pinfunction "IN2_10") (pintype "passive"))
    )
    (net (code "74") (name "Net-(U7-IN3)") (class "Default")
      (node (ref "FPC1") (pin "4") (pinfunction "4_4") (pintype "passive"))
      (node (ref "U7") (pin "9") (pinfunction "IN3_9") (pintype "passive"))
    )
    (net (code "75") (name "Net-(U7-IN4)") (class "Default")
      (node (ref "FPC1") (pin "6") (pinfunction "6_6") (pintype "passive"))
      (node (ref "U7") (pin "7") (pinfunction "IN4_7") (pintype "passive"))
    )
    (net (code "76") (name "Net-(U7-VCC)") (class "Default")
      (node (ref "R13") (pin "2") (pinfunction "2_2") (pintype "passive"))
      (node (ref "U7") (pin "2") (pinfunction "VCC_2") (pintype "passive"))
    )
    (net (code "77") (name "P3V3") (class "Default")
      (node (ref "C19") (pin "2") (pinfunction "2_2") (pintype "passive"))
      (node (ref "C23") (pin "2") (pinfunction "2_2") (pintype "passive"))
      (node (ref "JP2") (pin "2") (pinfunction "2_2") (pintype "passive"))
      (node (ref "JP3") (pin "6") (pinfunction "VCC_6") (pintype "passive"))
      (node (ref "JP8") (pin "2") (pinfunction "2_2") (pintype "passive"))
      (node (ref "JP8") (pin "8") (pinfunction "8_8") (pintype "passive"))
      (node (ref "U6") (pin "5") (pinfunction "OUT_5") (pintype "passive"))
    )
    (net (code "78") (name "PGND") (class "Default")
      (node (ref "R4") (pin "1") (pinfunction "1_1") (pintype "passive"))
      (node (ref "R5") (pin "1") (pinfunction "1_1") (pintype "passive"))
      (node (ref "R6") (pin "1") (pinfunction "1_1") (pintype "passive"))
      (node (ref "R7") (pin "1") (pinfunction "1_1") (pintype "passive"))
      (node (ref "U1") (pin "6") (pinfunction "GND_6") (pintype "passive"))
      (node (ref "U1") (pin "8") (pinfunction "GND_8") (pintype "passive"))
    )
    (net (code "79") (name "S3V3") (class "Default")
      (node (ref "C14") (pin "2") (pinfunction "2_2") (pintype "passive"))
      (node (ref "JP1") (pin "17") (pinfunction "17_17") (pintype "passive"))
      (node (ref "JP1") (pin "18") (pinfunction "18_18") (pintype "passive"))
      (node (ref "R13") (pin "1") (pinfunction "1_1") (pintype "passive"))
      (node (ref "U5") (pin "5") (pinfunction "OUT_5") (pintype "passive"))
    )
    (net (code "80") (name "VBAT") (class "Default")
      (node (ref "E2") (pin "1") (pinfunction "A_1") (pintype "passive"))
      (node (ref "POWER1") (pin "1") (pinfunction "VCC_1") (pintype "passive"))
      (node (ref "S1") (pin "2") (pinfunction "2_2") (pintype "passive"))
      (node (ref "U1") (pin "7") (pinfunction "VBAT_7") (pintype "passive"))
    )
    (net (code "81") (name "unconnected-(D1-DO-Pad4)") (class "Default")
      (node (ref "D1") (pin "4") (pinfunction "DO_4") (pintype "passive"))
    )
    (net (code "82") (name "unconnected-(JP1-Pad5)") (class "Default")
      (node (ref "JP1") (pin "5") (pinfunction "5_5") (pintype "passive"))
    )
    (net (code "83") (name "unconnected-(JP2-Pad7)") (class "Default")
      (node (ref "JP2") (pin "7") (pinfunction "7_7") (pintype "passive"))
    )
    (net (code "84") (name "unconnected-(JP2-Pad8)") (class "Default")
      (node (ref "JP2") (pin "8") (pinfunction "8_8") (pintype "passive"))
    )
    (net (code "85") (name "unconnected-(JP3-NC-Pad4)") (class "Default")
      (node (ref "JP3") (pin "4") (pinfunction "NC_4") (pintype "passive"))
    )
    (net (code "86") (name "unconnected-(JP3-Z-Pad3)") (class "Default")
      (node (ref "JP3") (pin "3") (pinfunction "Z_3") (pintype "passive"))
    )
    (net (code "87") (name "unconnected-(JP4-Pad2)") (class "Default")
      (node (ref "JP4") (pin "2") (pinfunction "2_2") (pintype "passive"))
    )
    (net (code "88") (name "unconnected-(JP4-Pad8)") (class "Default")
      (node (ref "JP4") (pin "8") (pinfunction "8_8") (pintype "passive"))
    )
    (net (code "89") (name "unconnected-(JP6-NC-Pad4)") (class "Default")
      (node (ref "JP6") (pin "4") (pinfunction "NC_4") (pintype "passive"))
    )
    (net (code "90") (name "unconnected-(JP6-Z-Pad3)") (class "Default")
      (node (ref "JP6") (pin "3") (pinfunction "Z_3") (pintype "passive"))
    )
    (net (code "91") (name "unconnected-(S1-Pad3)") (class "Default")
      (node (ref "S1") (pin "3") (pinfunction "3_3") (pintype "passive+no_connect"))
    )
    (net (code "92") (name "unconnected-(U4-PA4-Pad20)") (class "Default")
      (node (ref "U4") (pin "20") (pinfunction "PA4_20") (pintype "passive"))
    )
    (net (code "93") (name "unconnected-(U4-PA7-Pad23)") (class "Default")
      (node (ref "U4") (pin "23") (pinfunction "PA7_23") (pintype "passive"))
    )
    (net (code "94") (name "unconnected-(U4-PC2-Pad10)") (class "Default")
      (node (ref "U4") (pin "10") (pinfunction "PC2_10") (pintype "passive"))
    )
    (net (code "95") (name "unconnected-(U4-PC3-Pad11)") (class "Default")
      (node (ref "U4") (pin "11") (pinfunction "PC3_11") (pintype "passive"))
    )
  )
)
